# Seaquencer.net
KiCad netlist of a schematic drawn in EAGLE
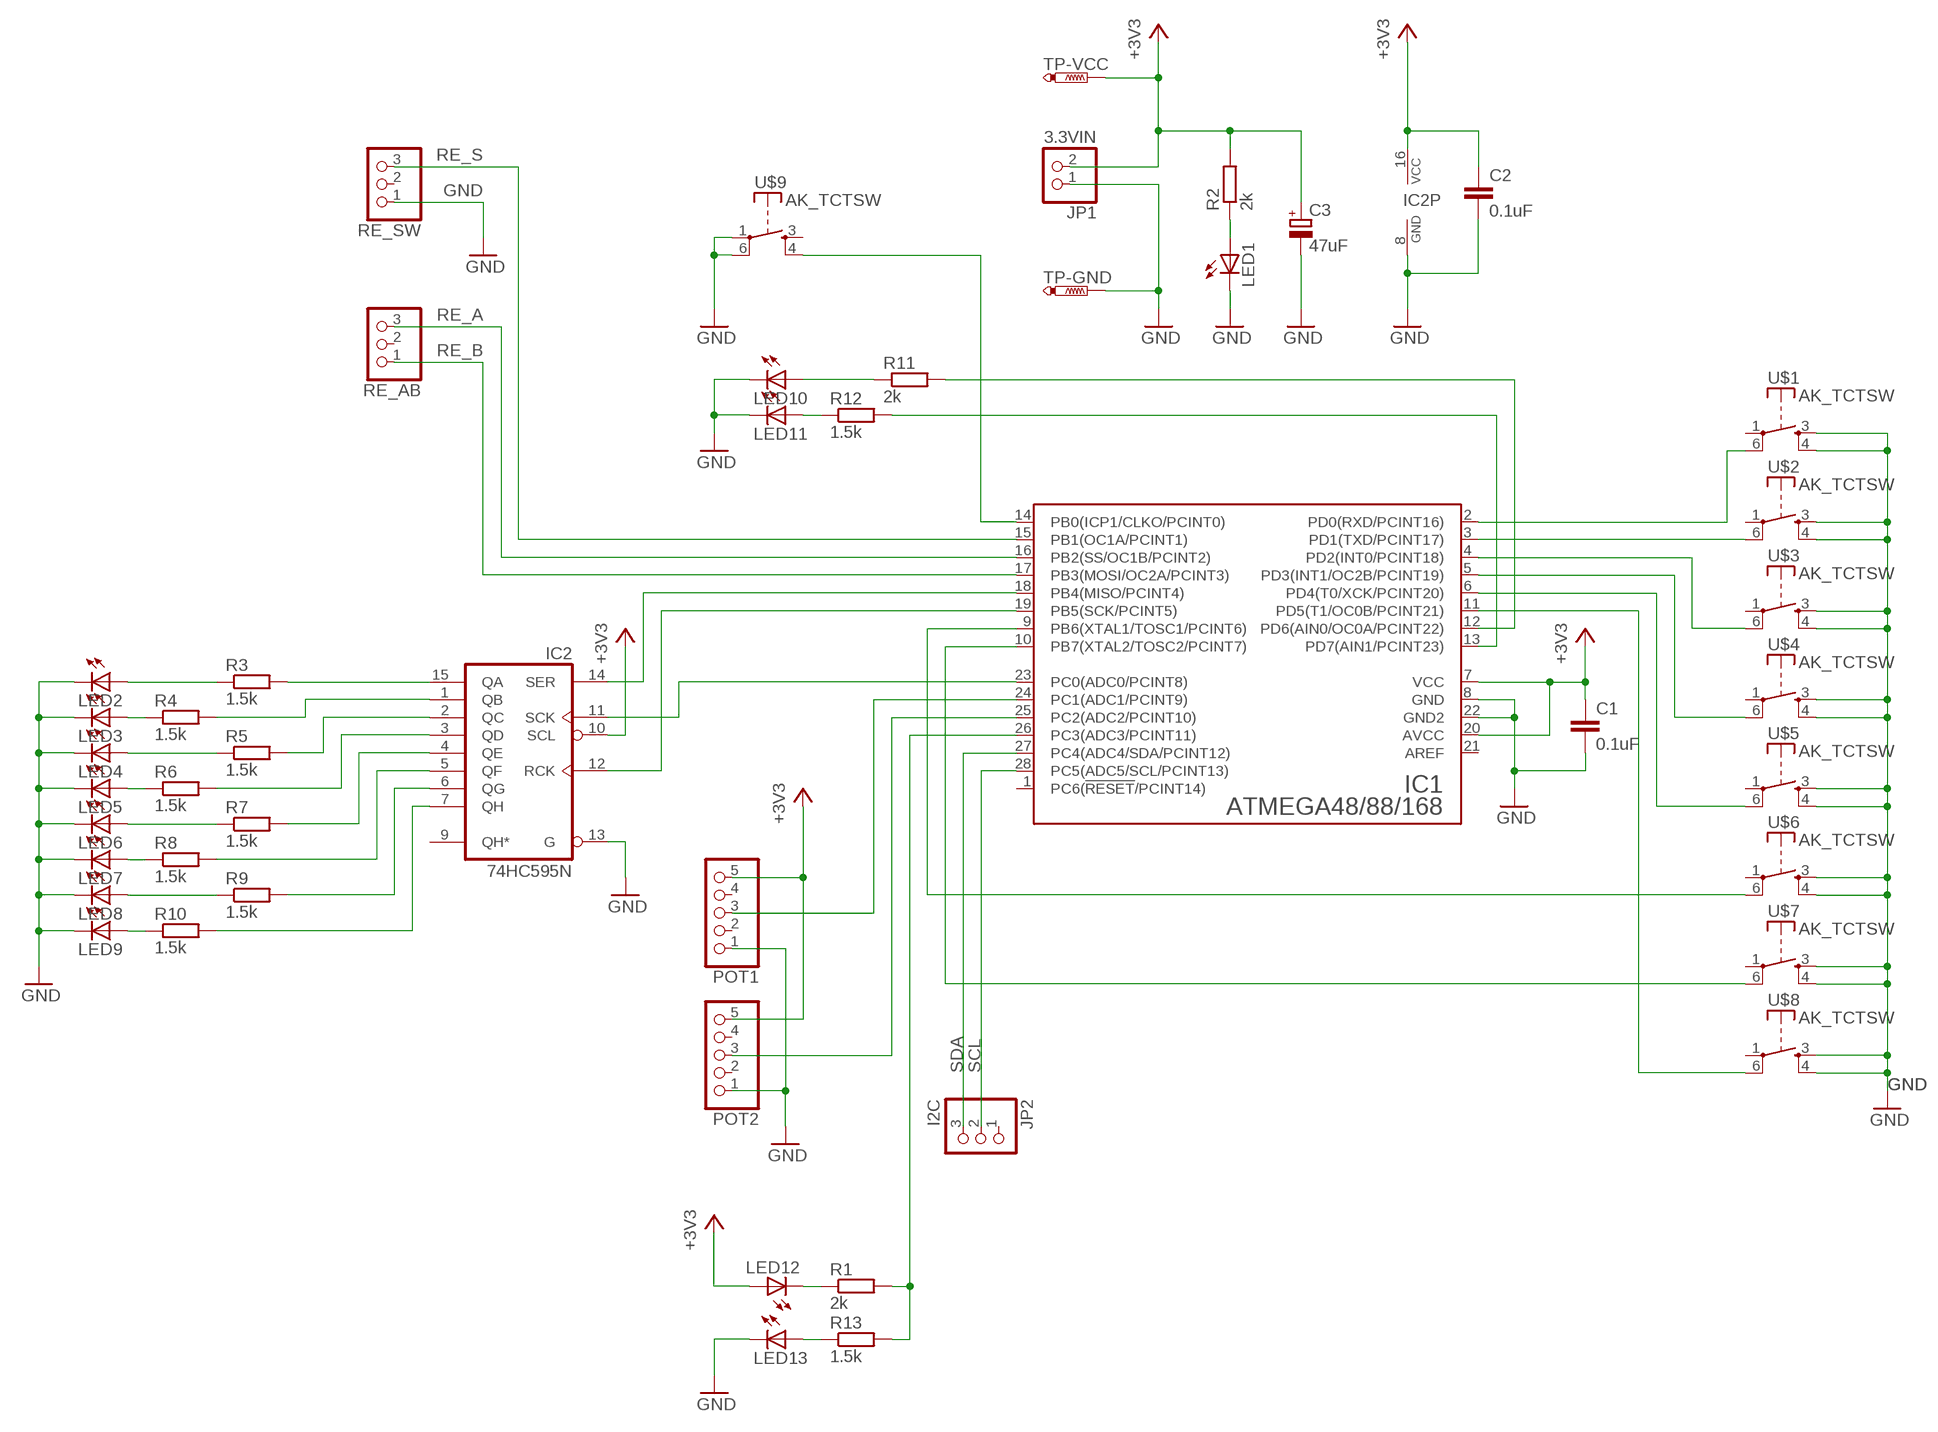
[diagram p0: schematic, sheet 1]

(export (version "E")
  (design (tool "Eeschema 10.0.6"))
  (components
    (comp (ref "C1")
      (value "0.1uF")
      (footprint "eagle-import:C025-024X044")
      (libsource (lib "eagle-import") (part "C-EU025-024X044"))
    )
    (comp (ref "C2")
      (value "0.1uF")
      (footprint "eagle-import:C025-024X044")
      (libsource (lib "eagle-import") (part "C-EU025-024X044"))
    )
    (comp (ref "C3")
      (value "47uF")
      (footprint "eagle-import:E2,5-6")
      (libsource (lib "eagle-import") (part "CPOL-EUE2.5-6"))
    )
    (comp (ref "IC1")
      (value "ATMEGA48/88/168")
      (footprint "eagle-import:DIL28-3")
      (libsource (lib "eagle-import") (part "ATMEGA48/88/168"))
    )
    (comp (ref "IC2")
      (value "74HC595N")
      (footprint "eagle-import:DIL16")
      (libsource (lib "eagle-import") (part "74595NHC"))
    )
    (comp (ref "JP1")
      (value "3.3VIN")
      (footprint "eagle-import:1X02_90")
      (libsource (lib "eagle-import") (part "PINHD-1X2/90"))
    )
    (comp (ref "JP2")
      (value "I2C")
      (footprint "eagle-import:1X03_90")
      (libsource (lib "eagle-import") (part "PINHD-1X3/90"))
    )
    (comp (ref "LED1")
      (value "LED3MM")
      (footprint "eagle-import:LED3MM")
      (libsource (lib "eagle-import") (part "LED3MM"))
    )
    (comp (ref "LED2")
      (value "LED3MM")
      (footprint "eagle-import:LED3MM")
      (libsource (lib "eagle-import") (part "LED3MM"))
    )
    (comp (ref "LED3")
      (value "LED3MM")
      (footprint "eagle-import:LED3MM")
      (libsource (lib "eagle-import") (part "LED3MM"))
    )
    (comp (ref "LED4")
      (value "LED3MM")
      (footprint "eagle-import:LED3MM")
      (libsource (lib "eagle-import") (part "LED3MM"))
    )
    (comp (ref "LED5")
      (value "LED3MM")
      (footprint "eagle-import:LED3MM")
      (libsource (lib "eagle-import") (part "LED3MM"))
    )
    (comp (ref "LED6")
      (value "LED3MM")
      (footprint "eagle-import:LED3MM")
      (libsource (lib "eagle-import") (part "LED3MM"))
    )
    (comp (ref "LED7")
      (value "LED3MM")
      (footprint "eagle-import:LED3MM")
      (libsource (lib "eagle-import") (part "LED3MM"))
    )
    (comp (ref "LED8")
      (value "LED3MM")
      (footprint "eagle-import:LED3MM")
      (libsource (lib "eagle-import") (part "LED3MM"))
    )
    (comp (ref "LED9")
      (value "LED3MM")
      (footprint "eagle-import:LED3MM")
      (libsource (lib "eagle-import") (part "LED3MM"))
    )
    (comp (ref "LED10")
      (value "LED3MM")
      (footprint "eagle-import:LED3MM")
      (libsource (lib "eagle-import") (part "LED3MM"))
    )
    (comp (ref "LED11")
      (value "LED3MM")
      (footprint "eagle-import:LED3MM")
      (libsource (lib "eagle-import") (part "LED3MM"))
    )
    (comp (ref "LED12")
      (value "LED3MM")
      (footprint "eagle-import:LED3MM")
      (libsource (lib "eagle-import") (part "LED3MM"))
    )
    (comp (ref "LED13")
      (value "LED3MM")
      (footprint "eagle-import:LED3MM")
      (libsource (lib "eagle-import") (part "LED3MM"))
    )
    (comp (ref "POT1")
      (value "PINHD-1X5")
      (footprint "eagle-import:1X05")
      (libsource (lib "eagle-import") (part "PINHD-1X5"))
    )
    (comp (ref "POT2")
      (value "PINHD-1X5")
      (footprint "eagle-import:1X05")
      (libsource (lib "eagle-import") (part "PINHD-1X5"))
    )
    (comp (ref "R1")
      (value "2k")
      (footprint "eagle-import:0207_7")
      (libsource (lib "eagle-import") (part "R-EU_0207/7"))
    )
    (comp (ref "R2")
      (value "2k")
      (footprint "eagle-import:0207_7")
      (libsource (lib "eagle-import") (part "R-EU_0207/7"))
    )
    (comp (ref "R3")
      (value "1.5k")
      (footprint "eagle-import:0207_7")
      (libsource (lib "eagle-import") (part "R-EU_0207/7"))
    )
    (comp (ref "R4")
      (value "1.5k")
      (footprint "eagle-import:0207_7")
      (libsource (lib "eagle-import") (part "R-EU_0207/7"))
    )
    (comp (ref "R5")
      (value "1.5k")
      (footprint "eagle-import:0207_7")
      (libsource (lib "eagle-import") (part "R-EU_0207/7"))
    )
    (comp (ref "R6")
      (value "1.5k")
      (footprint "eagle-import:0207_7")
      (libsource (lib "eagle-import") (part "R-EU_0207/7"))
    )
    (comp (ref "R7")
      (value "1.5k")
      (footprint "eagle-import:0207_7")
      (libsource (lib "eagle-import") (part "R-EU_0207/7"))
    )
    (comp (ref "R8")
      (value "1.5k")
      (footprint "eagle-import:0207_7")
      (libsource (lib "eagle-import") (part "R-EU_0207/7"))
    )
    (comp (ref "R9")
      (value "1.5k")
      (footprint "eagle-import:0207_7")
      (libsource (lib "eagle-import") (part "R-EU_0207/7"))
    )
    (comp (ref "R10")
      (value "1.5k")
      (footprint "eagle-import:0207_7")
      (libsource (lib "eagle-import") (part "R-EU_0207/7"))
    )
    (comp (ref "R11")
      (value "2k")
      (footprint "eagle-import:0207_7")
      (libsource (lib "eagle-import") (part "R-EU_0207/7"))
    )
    (comp (ref "R12")
      (value "1.5k")
      (footprint "eagle-import:0207_7")
      (libsource (lib "eagle-import") (part "R-EU_0207/7"))
    )
    (comp (ref "R13")
      (value "1.5k")
      (footprint "eagle-import:0207_7")
      (libsource (lib "eagle-import") (part "R-EU_0207/7"))
    )
    (comp (ref "RE_AB")
      (value "PINHD-1X3")
      (footprint "eagle-import:1X03")
      (libsource (lib "eagle-import") (part "PINHD-1X3"))
    )
    (comp (ref "RE_SW")
      (value "PINHD-1X3")
      (footprint "eagle-import:1X03")
      (libsource (lib "eagle-import") (part "PINHD-1X3"))
    )
    (comp (ref "TP-GND")
      (value "PTR1PAD1-13")
      (footprint "eagle-import:P1-13")
      (libsource (lib "eagle-import") (part "PTR1PAD1-13"))
    )
    (comp (ref "TP-VCC")
      (value "PTR1PAD1-13")
      (footprint "eagle-import:P1-13")
      (libsource (lib "eagle-import") (part "PTR1PAD1-13"))
    )
    (comp (ref "U$1")
      (value "AK_TCTSW")
      (footprint "eagle-import:TME1")
      (libsource (lib "eagle-import") (part "AK_TCTSW"))
    )
    (comp (ref "U$2")
      (value "AK_TCTSW")
      (footprint "eagle-import:TME1")
      (libsource (lib "eagle-import") (part "AK_TCTSW"))
    )
    (comp (ref "U$3")
      (value "AK_TCTSW")
      (footprint "eagle-import:TME1")
      (libsource (lib "eagle-import") (part "AK_TCTSW"))
    )
    (comp (ref "U$4")
      (value "AK_TCTSW")
      (footprint "eagle-import:TME1")
      (libsource (lib "eagle-import") (part "AK_TCTSW"))
    )
    (comp (ref "U$5")
      (value "AK_TCTSW")
      (footprint "eagle-import:TME1")
      (libsource (lib "eagle-import") (part "AK_TCTSW"))
    )
    (comp (ref "U$6")
      (value "AK_TCTSW")
      (footprint "eagle-import:TME1")
      (libsource (lib "eagle-import") (part "AK_TCTSW"))
    )
    (comp (ref "U$7")
      (value "AK_TCTSW")
      (footprint "eagle-import:TME1")
      (libsource (lib "eagle-import") (part "AK_TCTSW"))
    )
    (comp (ref "U$8")
      (value "AK_TCTSW")
      (footprint "eagle-import:TME1")
      (libsource (lib "eagle-import") (part "AK_TCTSW"))
    )
    (comp (ref "U$9")
      (value "AK_TCTSW")
      (footprint "eagle-import:TME1")
      (libsource (lib "eagle-import") (part "AK_TCTSW"))
    )
  )
  (nets
    (net (code "1") (name "+3V3") (class "Default")
      (node (ref "C1") (pin "1") (pinfunction "1_1") (pintype "passive"))
      (node (ref "C2") (pin "1") (pinfunction "1_1") (pintype "passive"))
      (node (ref "C3") (pin "+") (pinfunction "+_+") (pintype "passive"))
      (node (ref "IC1") (pin "20") (pinfunction "AVCC_20") (pintype "power_in"))
      (node (ref "IC1") (pin "7") (pinfunction "VCC_7") (pintype "power_in"))
      (node (ref "IC2") (pin "10") (pinfunction "SCL_10") (pintype "input"))
      (node (ref "IC2") (pin "16") (pinfunction "VCC_16") (pintype "power_in"))
      (node (ref "JP1") (pin "2") (pinfunction "2_2") (pintype "passive"))
      (node (ref "LED12") (pin "A") (pinfunction "A_A") (pintype "passive"))
      (node (ref "POT1") (pin "5") (pinfunction "5_5") (pintype "passive"))
      (node (ref "POT2") (pin "5") (pinfunction "5_5") (pintype "passive"))
      (node (ref "R2") (pin "2") (pinfunction "2_2") (pintype "passive"))
      (node (ref "TP-VCC") (pin "TP") (pinfunction "TP_TP") (pintype "input"))
    )
    (net (code "2") (name "/RE_A") (class "Default")
      (node (ref "IC1") (pin "16") (pinfunction "PB2(SS/OC1B/PCINT2)_16") (pintype "bidirectional"))
      (node (ref "RE_AB") (pin "3") (pinfunction "3_3") (pintype "passive"))
    )
    (net (code "3") (name "/RE_B") (class "Default")
      (node (ref "IC1") (pin "17") (pinfunction "PB3(MOSI/OC2A/PCINT3)_17") (pintype "bidirectional"))
      (node (ref "RE_AB") (pin "1") (pinfunction "1_1") (pintype "passive"))
    )
    (net (code "4") (name "/RE_S") (class "Default")
      (node (ref "IC1") (pin "15") (pinfunction "PB1(OC1A/PCINT1)_15") (pintype "bidirectional"))
      (node (ref "RE_SW") (pin "3") (pinfunction "3_3") (pintype "passive"))
    )
    (net (code "5") (name "/SCL") (class "Default")
      (node (ref "IC1") (pin "28") (pinfunction "PC5(ADC5/SCL/PCINT13)_28") (pintype "bidirectional"))
      (node (ref "JP2") (pin "2") (pinfunction "2_2") (pintype "passive"))
    )
    (net (code "6") (name "/SDA") (class "Default")
      (node (ref "IC1") (pin "27") (pinfunction "PC4(ADC4/SDA/PCINT12)_27") (pintype "bidirectional"))
      (node (ref "JP2") (pin "3") (pinfunction "3_3") (pintype "passive"))
    )
    (net (code "7") (name "GND") (class "Default")
      (node (ref "C1") (pin "2") (pinfunction "2_2") (pintype "passive"))
      (node (ref "C2") (pin "2") (pinfunction "2_2") (pintype "passive"))
      (node (ref "C3") (pin "-") (pinfunction "-_-") (pintype "passive"))
      (node (ref "IC1") (pin "22") (pinfunction "GND2_22") (pintype "power_in"))
      (node (ref "IC1") (pin "8") (pinfunction "GND_8") (pintype "power_in"))
      (node (ref "IC2") (pin "13") (pinfunction "G_13") (pintype "input"))
      (node (ref "IC2") (pin "8") (pinfunction "GND_8") (pintype "power_in"))
      (node (ref "JP1") (pin "1") (pinfunction "1_1") (pintype "passive"))
      (node (ref "LED1") (pin "K") (pinfunction "C_K") (pintype "passive"))
      (node (ref "LED10") (pin "K") (pinfunction "C_K") (pintype "passive"))
      (node (ref "LED11") (pin "K") (pinfunction "C_K") (pintype "passive"))
      (node (ref "LED13") (pin "K") (pinfunction "C_K") (pintype "passive"))
      (node (ref "LED2") (pin "K") (pinfunction "C_K") (pintype "passive"))
      (node (ref "LED3") (pin "K") (pinfunction "C_K") (pintype "passive"))
      (node (ref "LED4") (pin "K") (pinfunction "C_K") (pintype "passive"))
      (node (ref "LED5") (pin "K") (pinfunction "C_K") (pintype "passive"))
      (node (ref "LED6") (pin "K") (pinfunction "C_K") (pintype "passive"))
      (node (ref "LED7") (pin "K") (pinfunction "C_K") (pintype "passive"))
      (node (ref "LED8") (pin "K") (pinfunction "C_K") (pintype "passive"))
      (node (ref "LED9") (pin "K") (pinfunction "C_K") (pintype "passive"))
      (node (ref "POT1") (pin "1") (pinfunction "1_1") (pintype "passive"))
      (node (ref "POT2") (pin "1") (pinfunction "1_1") (pintype "passive"))
      (node (ref "RE_SW") (pin "1") (pinfunction "1_1") (pintype "passive"))
      (node (ref "TP-GND") (pin "TP") (pinfunction "TP_TP") (pintype "input"))
      (node (ref "U$1") (pin "3") (pinfunction "S_3") (pintype "passive"))
      (node (ref "U$1") (pin "4") (pinfunction "S_4") (pintype "passive"))
      (node (ref "U$2") (pin "3") (pinfunction "S_3") (pintype "passive"))
      (node (ref "U$2") (pin "4") (pinfunction "S_4") (pintype "passive"))
      (node (ref "U$3") (pin "3") (pinfunction "S_3") (pintype "passive"))
      (node (ref "U$3") (pin "4") (pinfunction "S_4") (pintype "passive"))
      (node (ref "U$4") (pin "3") (pinfunction "S_3") (pintype "passive"))
      (node (ref "U$4") (pin "4") (pinfunction "S_4") (pintype "passive"))
      (node (ref "U$5") (pin "3") (pinfunction "S_3") (pintype "passive"))
      (node (ref "U$5") (pin "4") (pinfunction "S_4") (pintype "passive"))
      (node (ref "U$6") (pin "3") (pinfunction "S_3") (pintype "passive"))
      (node (ref "U$6") (pin "4") (pinfunction "S_4") (pintype "passive"))
      (node (ref "U$7") (pin "3") (pinfunction "S_3") (pintype "passive"))
      (node (ref "U$7") (pin "4") (pinfunction "S_4") (pintype "passive"))
      (node (ref "U$8") (pin "3") (pinfunction "S_3") (pintype "passive"))
      (node (ref "U$8") (pin "4") (pinfunction "S_4") (pintype "passive"))
      (node (ref "U$9") (pin "1") (pinfunction "P_1") (pintype "passive"))
      (node (ref "U$9") (pin "6") (pinfunction "P_6") (pintype "passive"))
    )
    (net (code "8") (name "Net-(IC1-PB0(ICP1{slash}CLKO{slash}PCINT0))") (class "Default")
      (node (ref "IC1") (pin "14") (pinfunction "PB0(ICP1/CLKO/PCINT0)_14") (pintype "bidirectional"))
      (node (ref "U$9") (pin "4") (pinfunction "S_4") (pintype "passive"))
    )
    (net (code "9") (name "Net-(IC1-PB4(MISO{slash}PCINT4))") (class "Default")
      (node (ref "IC1") (pin "18") (pinfunction "PB4(MISO/PCINT4)_18") (pintype "bidirectional"))
      (node (ref "IC2") (pin "14") (pinfunction "SER_14") (pintype "input"))
    )
    (net (code "10") (name "Net-(IC1-PB5(SCK{slash}PCINT5))") (class "Default")
      (node (ref "IC1") (pin "19") (pinfunction "PB5(SCK/PCINT5)_19") (pintype "bidirectional"))
      (node (ref "IC2") (pin "12") (pinfunction "RCK_12") (pintype "input"))
    )
    (net (code "11") (name "Net-(IC1-PB6(XTAL1{slash}TOSC1{slash}PCINT6))") (class "Default")
      (node (ref "IC1") (pin "9") (pinfunction "PB6(XTAL1/TOSC1/PCINT6)_9") (pintype "bidirectional"))
      (node (ref "U$6") (pin "6") (pinfunction "P_6") (pintype "passive"))
    )
    (net (code "12") (name "Net-(IC1-PB7(XTAL2{slash}TOSC2{slash}PCINT7))") (class "Default")
      (node (ref "IC1") (pin "10") (pinfunction "PB7(XTAL2/TOSC2/PCINT7)_10") (pintype "bidirectional"))
      (node (ref "U$7") (pin "6") (pinfunction "P_6") (pintype "passive"))
    )
    (net (code "13") (name "Net-(IC1-PC0(ADC0{slash}PCINT8))") (class "Default")
      (node (ref "IC1") (pin "23") (pinfunction "PC0(ADC0/PCINT8)_23") (pintype "bidirectional"))
      (node (ref "IC2") (pin "11") (pinfunction "SCK_11") (pintype "input"))
    )
    (net (code "14") (name "Net-(IC1-PC1(ADC1{slash}PCINT9))") (class "Default")
      (node (ref "IC1") (pin "24") (pinfunction "PC1(ADC1/PCINT9)_24") (pintype "bidirectional"))
      (node (ref "POT1") (pin "3") (pinfunction "3_3") (pintype "passive"))
    )
    (net (code "15") (name "Net-(IC1-PC2(ADC2{slash}PCINT10))") (class "Default")
      (node (ref "IC1") (pin "25") (pinfunction "PC2(ADC2/PCINT10)_25") (pintype "bidirectional"))
      (node (ref "POT2") (pin "3") (pinfunction "3_3") (pintype "passive"))
    )
    (net (code "16") (name "Net-(IC1-PC3(ADC3{slash}PCINT11))") (class "Default")
      (node (ref "IC1") (pin "26") (pinfunction "PC3(ADC3/PCINT11)_26") (pintype "bidirectional"))
      (node (ref "R1") (pin "2") (pinfunction "2_2") (pintype "passive"))
      (node (ref "R13") (pin "2") (pinfunction "2_2") (pintype "passive"))
    )
    (net (code "17") (name "Net-(IC1-PD0(RXD{slash}PCINT16))") (class "Default")
      (node (ref "IC1") (pin "2") (pinfunction "PD0(RXD/PCINT16)_2") (pintype "bidirectional"))
      (node (ref "U$1") (pin "6") (pinfunction "P_6") (pintype "passive"))
    )
    (net (code "18") (name "Net-(IC1-PD1(TXD{slash}PCINT17))") (class "Default")
      (node (ref "IC1") (pin "3") (pinfunction "PD1(TXD/PCINT17)_3") (pintype "bidirectional"))
      (node (ref "U$2") (pin "6") (pinfunction "P_6") (pintype "passive"))
    )
    (net (code "19") (name "Net-(IC1-PD2(INT0{slash}PCINT18))") (class "Default")
      (node (ref "IC1") (pin "4") (pinfunction "PD2(INT0/PCINT18)_4") (pintype "bidirectional"))
      (node (ref "U$3") (pin "6") (pinfunction "P_6") (pintype "passive"))
    )
    (net (code "20") (name "Net-(IC1-PD3(INT1{slash}OC2B{slash}PCINT19))") (class "Default")
      (node (ref "IC1") (pin "5") (pinfunction "PD3(INT1/OC2B/PCINT19)_5") (pintype "bidirectional"))
      (node (ref "U$4") (pin "6") (pinfunction "P_6") (pintype "passive"))
    )
    (net (code "21") (name "Net-(IC1-PD4(T0{slash}XCK{slash}PCINT20))") (class "Default")
      (node (ref "IC1") (pin "6") (pinfunction "PD4(T0/XCK/PCINT20)_6") (pintype "bidirectional"))
      (node (ref "U$5") (pin "6") (pinfunction "P_6") (pintype "passive"))
    )
    (net (code "22") (name "Net-(IC1-PD5(T1{slash}OC0B{slash}PCINT21))") (class "Default")
      (node (ref "IC1") (pin "11") (pinfunction "PD5(T1/OC0B/PCINT21)_11") (pintype "bidirectional"))
      (node (ref "U$8") (pin "6") (pinfunction "P_6") (pintype "passive"))
    )
    (net (code "23") (name "Net-(IC1-PD6(AIN0{slash}OC0A{slash}PCINT22))") (class "Default")
      (node (ref "IC1") (pin "12") (pinfunction "PD6(AIN0/OC0A/PCINT22)_12") (pintype "bidirectional"))
      (node (ref "R11") (pin "2") (pinfunction "2_2") (pintype "passive"))
    )
    (net (code "24") (name "Net-(IC1-PD7(AIN1{slash}PCINT23))") (class "Default")
      (node (ref "IC1") (pin "13") (pinfunction "PD7(AIN1/PCINT23)_13") (pintype "bidirectional"))
      (node (ref "R12") (pin "2") (pinfunction "2_2") (pintype "passive"))
    )
    (net (code "25") (name "Net-(IC2A-QA)") (class "Default")
      (node (ref "IC2") (pin "15") (pinfunction "QA_15") (pintype "tri_state"))
      (node (ref "R3") (pin "2") (pinfunction "2_2") (pintype "passive"))
    )
    (net (code "26") (name "Net-(IC2A-QB)") (class "Default")
      (node (ref "IC2") (pin "1") (pinfunction "QB_1") (pintype "tri_state"))
      (node (ref "R4") (pin "2") (pinfunction "2_2") (pintype "passive"))
    )
    (net (code "27") (name "Net-(IC2A-QC)") (class "Default")
      (node (ref "IC2") (pin "2") (pinfunction "QC_2") (pintype "tri_state"))
      (node (ref "R5") (pin "2") (pinfunction "2_2") (pintype "passive"))
    )
    (net (code "28") (name "Net-(IC2A-QD)") (class "Default")
      (node (ref "IC2") (pin "3") (pinfunction "QD_3") (pintype "tri_state"))
      (node (ref "R6") (pin "2") (pinfunction "2_2") (pintype "passive"))
    )
    (net (code "29") (name "Net-(IC2A-QE)") (class "Default")
      (node (ref "IC2") (pin "4") (pinfunction "QE_4") (pintype "tri_state"))
      (node (ref "R7") (pin "2") (pinfunction "2_2") (pintype "passive"))
    )
    (net (code "30") (name "Net-(IC2A-QF)") (class "Default")
      (node (ref "IC2") (pin "5") (pinfunction "QF_5") (pintype "tri_state"))
      (node (ref "R8") (pin "2") (pinfunction "2_2") (pintype "passive"))
    )
    (net (code "31") (name "Net-(IC2A-QG)") (class "Default")
      (node (ref "IC2") (pin "6") (pinfunction "QG_6") (pintype "tri_state"))
      (node (ref "R9") (pin "2") (pinfunction "2_2") (pintype "passive"))
    )
    (net (code "32") (name "Net-(IC2A-QH)") (class "Default")
      (node (ref "IC2") (pin "7") (pinfunction "QH_7") (pintype "tri_state"))
      (node (ref "R10") (pin "2") (pinfunction "2_2") (pintype "passive"))
    )
    (net (code "33") (name "Net-(LED1-PadA)") (class "Default")
      (node (ref "LED1") (pin "A") (pinfunction "A_A") (pintype "passive"))
      (node (ref "R2") (pin "1") (pinfunction "1_1") (pintype "passive"))
    )
    (net (code "34") (name "Net-(LED2-PadA)") (class "Default")
      (node (ref "LED2") (pin "A") (pinfunction "A_A") (pintype "passive"))
      (node (ref "R3") (pin "1") (pinfunction "1_1") (pintype "passive"))
    )
    (net (code "35") (name "Net-(LED3-PadA)") (class "Default")
      (node (ref "LED3") (pin "A") (pinfunction "A_A") (pintype "passive"))
      (node (ref "R4") (pin "1") (pinfunction "1_1") (pintype "passive"))
    )
    (net (code "36") (name "Net-(LED4-PadA)") (class "Default")
      (node (ref "LED4") (pin "A") (pinfunction "A_A") (pintype "passive"))
      (node (ref "R5") (pin "1") (pinfunction "1_1") (pintype "passive"))
    )
    (net (code "37") (name "Net-(LED5-PadA)") (class "Default")
      (node (ref "LED5") (pin "A") (pinfunction "A_A") (pintype "passive"))
      (node (ref "R6") (pin "1") (pinfunction "1_1") (pintype "passive"))
    )
    (net (code "38") (name "Net-(LED6-PadA)") (class "Default")
      (node (ref "LED6") (pin "A") (pinfunction "A_A") (pintype "passive"))
      (node (ref "R7") (pin "1") (pinfunction "1_1") (pintype "passive"))
    )
    (net (code "39") (name "Net-(LED7-PadA)") (class "Default")
      (node (ref "LED7") (pin "A") (pinfunction "A_A") (pintype "passive"))
      (node (ref "R8") (pin "1") (pinfunction "1_1") (pintype "passive"))
    )
    (net (code "40") (name "Net-(LED8-PadA)") (class "Default")
      (node (ref "LED8") (pin "A") (pinfunction "A_A") (pintype "passive"))
      (node (ref "R9") (pin "1") (pinfunction "1_1") (pintype "passive"))
    )
    (net (code "41") (name "Net-(LED9-PadA)") (class "Default")
      (node (ref "LED9") (pin "A") (pinfunction "A_A") (pintype "passive"))
      (node (ref "R10") (pin "1") (pinfunction "1_1") (pintype "passive"))
    )
    (net (code "42") (name "Net-(LED10-PadA)") (class "Default")
      (node (ref "LED10") (pin "A") (pinfunction "A_A") (pintype "passive"))
      (node (ref "R11") (pin "1") (pinfunction "1_1") (pintype "passive"))
    )
    (net (code "43") (name "Net-(LED11-PadA)") (class "Default")
      (node (ref "LED11") (pin "A") (pinfunction "A_A") (pintype "passive"))
      (node (ref "R12") (pin "1") (pinfunction "1_1") (pintype "passive"))
    )
    (net (code "44") (name "Net-(LED12-C)") (class "Default")
      (node (ref "LED12") (pin "K") (pinfunction "C_K") (pintype "passive"))
      (node (ref "R1") (pin "1") (pinfunction "1_1") (pintype "passive"))
    )
    (net (code "45") (name "Net-(LED13-PadA)") (class "Default")
      (node (ref "LED13") (pin "A") (pinfunction "A_A") (pintype "passive"))
      (node (ref "R13") (pin "1") (pinfunction "1_1") (pintype "passive"))
    )
    (net (code "46") (name "unconnected-(IC1-AREF-Pad21)") (class "Default")
      (node (ref "IC1") (pin "21") (pinfunction "AREF_21") (pintype "passive"))
    )
    (net (code "47") (name "unconnected-(IC1-PC6(~{RESET}{slash}PCINT14)-Pad1)") (class "Default")
      (node (ref "IC1") (pin "1") (pinfunction "PC6(~{RESET}/PCINT14)_1") (pintype "bidirectional"))
    )
    (net (code "48") (name "unconnected-(IC2A-QH*-Pad9)") (class "Default")
      (node (ref "IC2") (pin "9") (pinfunction "QH*_9") (pintype "tri_state"))
    )
    (net (code "49") (name "unconnected-(JP2-Pad1)") (class "Default")
      (node (ref "JP2") (pin "1") (pinfunction "1_1") (pintype "passive"))
    )
    (net (code "50") (name "unconnected-(POT1-Pad2)") (class "Default")
      (node (ref "POT1") (pin "2") (pinfunction "2_2") (pintype "passive"))
    )
    (net (code "51") (name "unconnected-(POT1-Pad4)") (class "Default")
      (node (ref "POT1") (pin "4") (pinfunction "4_4") (pintype "passive"))
    )
    (net (code "52") (name "unconnected-(POT2-Pad2)") (class "Default")
      (node (ref "POT2") (pin "2") (pinfunction "2_2") (pintype "passive"))
    )
    (net (code "53") (name "unconnected-(POT2-Pad4)") (class "Default")
      (node (ref "POT2") (pin "4") (pinfunction "4_4") (pintype "passive"))
    )
    (net (code "54") (name "unconnected-(RE_AB-Pad2)") (class "Default")
      (node (ref "RE_AB") (pin "2") (pinfunction "2_2") (pintype "passive"))
    )
    (net (code "55") (name "unconnected-(RE_SW-Pad2)") (class "Default")
      (node (ref "RE_SW") (pin "2") (pinfunction "2_2") (pintype "passive"))
    )
    (net (code "56") (name "unconnected-(U$1-P-Pad1)") (class "Default")
      (node (ref "U$1") (pin "1") (pinfunction "P_1") (pintype "passive"))
    )
    (net (code "57") (name "unconnected-(U$2-P-Pad1)") (class "Default")
      (node (ref "U$2") (pin "1") (pinfunction "P_1") (pintype "passive"))
    )
    (net (code "58") (name "unconnected-(U$3-P-Pad1)") (class "Default")
      (node (ref "U$3") (pin "1") (pinfunction "P_1") (pintype "passive"))
    )
    (net (code "59") (name "unconnected-(U$4-P-Pad1)") (class "Default")
      (node (ref "U$4") (pin "1") (pinfunction "P_1") (pintype "passive"))
    )
    (net (code "60") (name "unconnected-(U$5-P-Pad1)") (class "Default")
      (node (ref "U$5") (pin "1") (pinfunction "P_1") (pintype "passive"))
    )
    (net (code "61") (name "unconnected-(U$6-P-Pad1)") (class "Default")
      (node (ref "U$6") (pin "1") (pinfunction "P_1") (pintype "passive"))
    )
    (net (code "62") (name "unconnected-(U$7-P-Pad1)") (class "Default")
      (node (ref "U$7") (pin "1") (pinfunction "P_1") (pintype "passive"))
    )
    (net (code "63") (name "unconnected-(U$8-P-Pad1)") (class "Default")
      (node (ref "U$8") (pin "1") (pinfunction "P_1") (pintype "passive"))
    )
    (net (code "64") (name "unconnected-(U$9-S-Pad3)") (class "Default")
      (node (ref "U$9") (pin "3") (pinfunction "S_3") (pintype "passive"))
    )
  )
)
